# project_vostok__tv_b_gone_extended.net
KiCad netlist of a schematic drawn in EAGLE
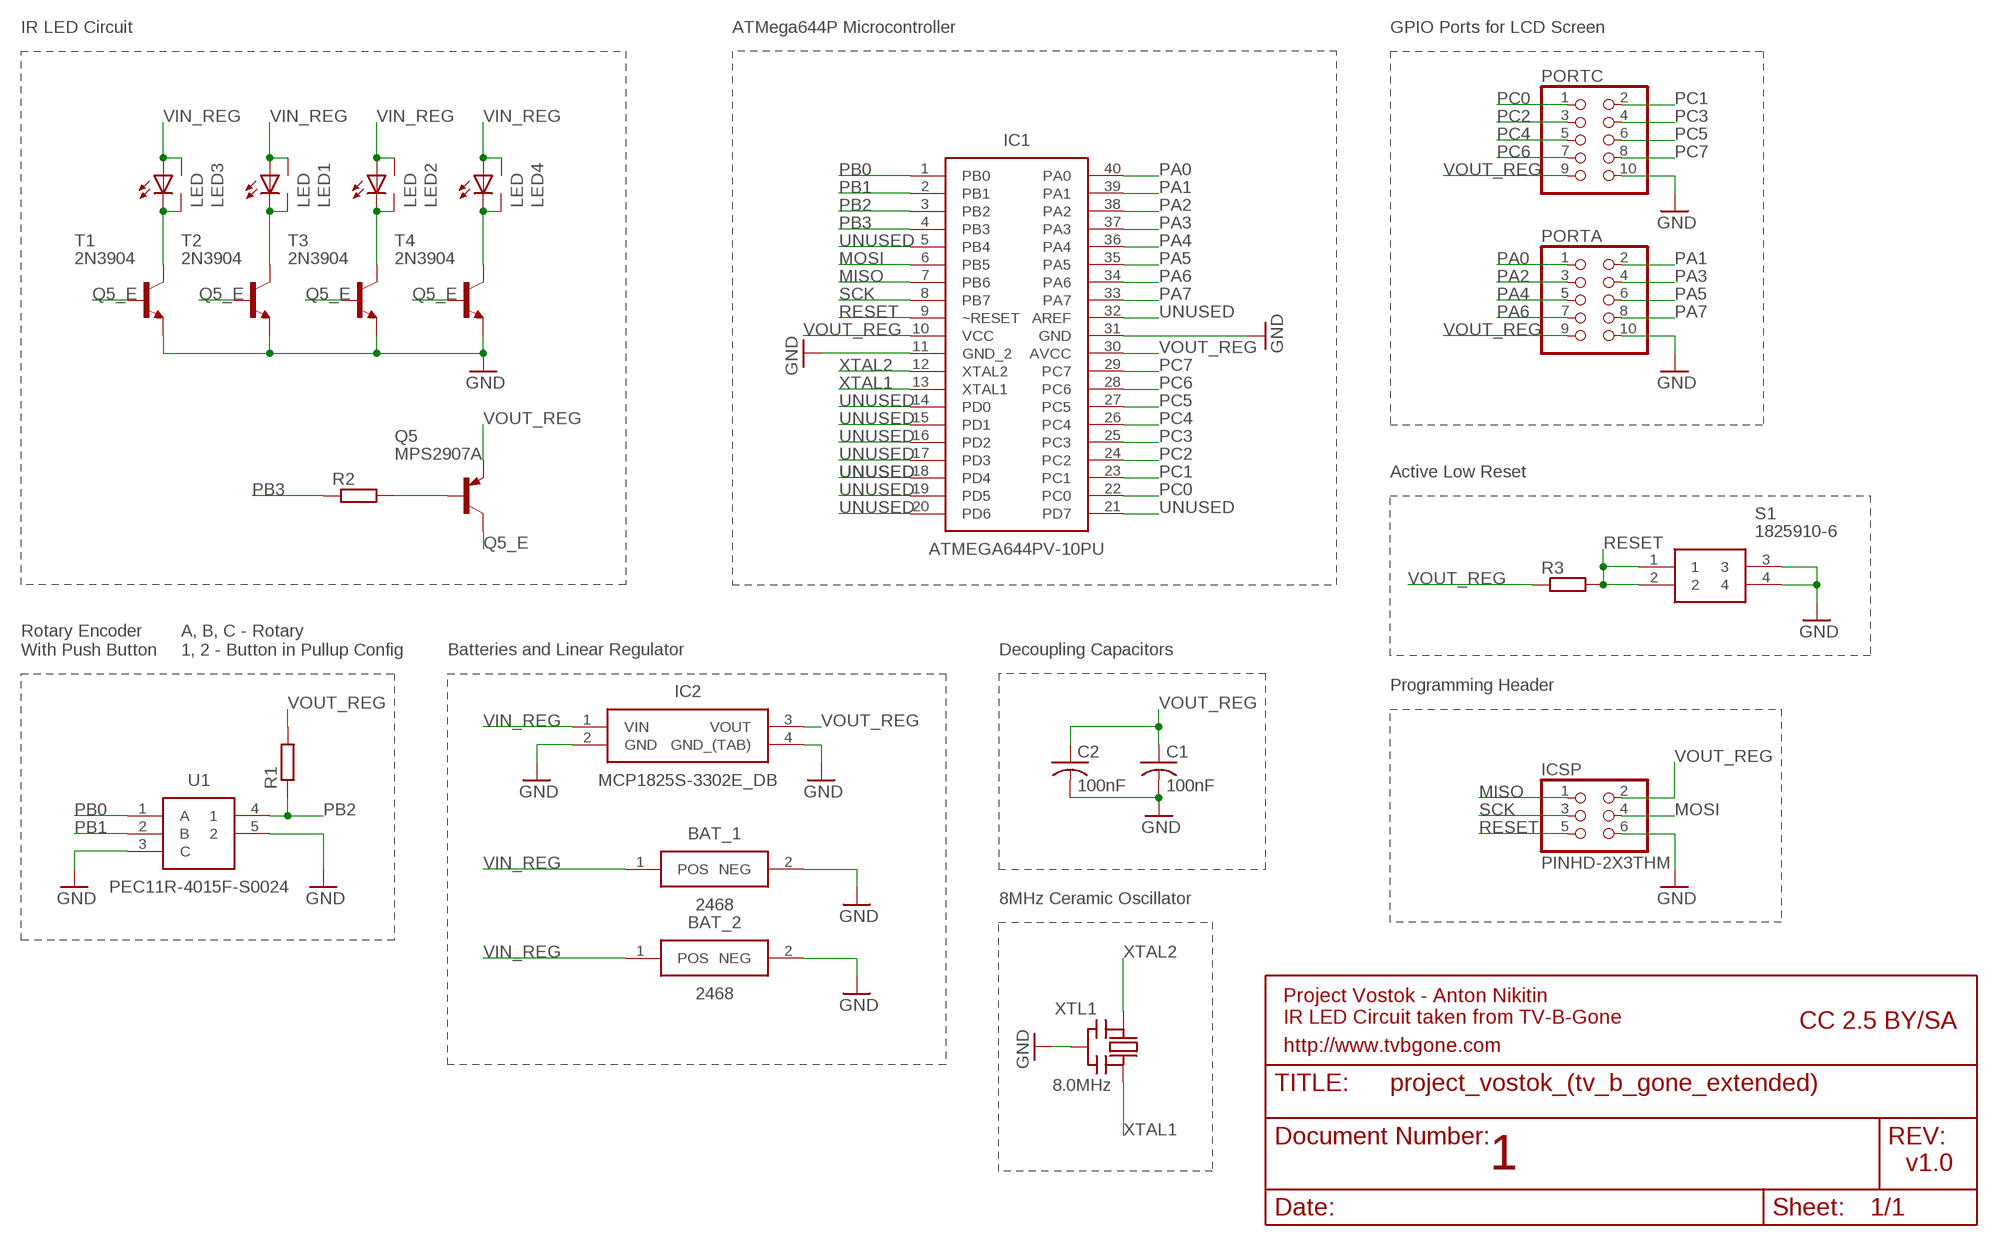
[diagram p0: schematic, sheet 1]

(export (version "E")
  (design (tool "Eeschema 10.0.6"))
  (components
    (comp (ref "BAT_1")
      (value "2468")
      (footprint "eagle-import:2468")
      (fields (field (name "RS_PART_NUMBER") "2794965"))
      (libsource (lib "eagle-import") (part "2468"))
    )
    (comp (ref "BAT_2")
      (value "2468")
      (footprint "eagle-import:2468")
      (fields (field (name "RS_PART_NUMBER") "2794965"))
      (libsource (lib "eagle-import") (part "2468"))
    )
    (comp (ref "C1")
      (value "100nF")
      (footprint "eagle-import:C025-025X050")
      (libsource (lib "eagle-import") (part "C-US025-025X050"))
    )
    (comp (ref "C2")
      (value "100nF")
      (footprint "eagle-import:C025-025X050")
      (libsource (lib "eagle-import") (part "C-US025-025X050"))
    )
    (comp (ref "IC1")
      (value "ATMEGA644PV-10PU")
      (footprint "eagle-import:DIP254P1524X483-40")
      (fields (field (name "RS_PART_NUMBER") "7380491P"))
      (libsource (lib "eagle-import") (part "ATMEGA644PV-10PU"))
    )
    (comp (ref "IC2")
      (value "MCP1825S-3302E_DB")
      (footprint "eagle-import:SOT230P700X180-4N")
      (fields
        (field (name "MANUFACTURER_PART_NUMBER") "MCP1825S-3302E/DB")
        (field (name "RS_PART_NUMBER") "9115520")
      )
      (libsource (lib "eagle-import") (part "MCP1825S-3302E_DB"))
    )
    (comp (ref "ICSP")
      (value "PINHD-2X3THM")
      (footprint "eagle-import:ISP6")
      (libsource (lib "eagle-import") (part "PINHD-2X3THM"))
    )
    (comp (ref "LED1")
      (value "LED")
      (footprint "eagle-import:5MM-SIDE")
      (libsource (lib "eagle-import") (part "LED"))
    )
    (comp (ref "LED2")
      (value "LED")
      (footprint "eagle-import:5MM-SIDE")
      (libsource (lib "eagle-import") (part "LED"))
    )
    (comp (ref "LED3")
      (value "LED")
      (footprint "eagle-import:5MM-SIDE")
      (libsource (lib "eagle-import") (part "LED"))
    )
    (comp (ref "LED4")
      (value "LED")
      (footprint "eagle-import:5MM-SIDE")
      (libsource (lib "eagle-import") (part "LED"))
    )
    (comp (ref "PORTA")
      (value "PINHD-2X5")
      (footprint "eagle-import:2X05")
      (libsource (lib "eagle-import") (part "PINHD-2X5"))
    )
    (comp (ref "PORTC")
      (value "PINHD-2X5")
      (footprint "eagle-import:2X05")
      (libsource (lib "eagle-import") (part "PINHD-2X5"))
    )
    (comp (ref "Q5")
      (value "MPS2907A")
      (footprint "eagle-import:TO92-CBE")
      (libsource (lib "eagle-import") (part "MPS2907A"))
    )
    (comp (ref "R1")
      (value "R-EU_0204/5")
      (footprint "eagle-import:0204_5")
      (libsource (lib "eagle-import") (part "resistor_348_R-EU_0204/5"))
    )
    (comp (ref "R2")
      (value "R-EU_0204/5")
      (footprint "eagle-import:0204_5")
      (libsource (lib "eagle-import") (part "resistor_348_R-EU_0204/5"))
    )
    (comp (ref "R3")
      (value "R-EU_0204/7")
      (footprint "eagle-import:0204_7")
      (libsource (lib "eagle-import") (part "R-EU_0204/7"))
    )
    (comp (ref "S1")
      (value "1825910-6")
      (footprint "eagle-import:1825910-6")
      (fields (field (name "RS_PART_NUMBER") "1613779"))
      (libsource (lib "eagle-import") (part "1825910-6"))
    )
    (comp (ref "T1")
      (value "2N3904")
      (footprint "eagle-import:TO92")
      (libsource (lib "eagle-import") (part "2N3904"))
    )
    (comp (ref "T2")
      (value "2N3904")
      (footprint "eagle-import:TO92")
      (libsource (lib "eagle-import") (part "2N3904"))
    )
    (comp (ref "T3")
      (value "2N3904")
      (footprint "eagle-import:TO92")
      (libsource (lib "eagle-import") (part "2N3904"))
    )
    (comp (ref "T4")
      (value "2N3904")
      (footprint "eagle-import:TO92")
      (libsource (lib "eagle-import") (part "2N3904"))
    )
    (comp (ref "U1")
      (value "PEC11R-4015F-S0024")
      (footprint "eagle-import:PEC12R-4XXXF-SXXXX_1")
      (fields (field (name "RS_PART_NUMBER") "7377739P"))
      (libsource (lib "eagle-import") (part "PEC11R-4015F-S0024"))
    )
    (comp (ref "XTL1")
      (value "8.0MHz")
      (footprint "eagle-import:CERM_OSC")
      (libsource (lib "eagle-import") (part "CERMOSCILL"))
    )
  )
  (nets
    (net (code "1") (name "/MISO") (class "Default")
      (node (ref "IC1") (pin "7") (pinfunction "PB6_7") (pintype "passive"))
      (node (ref "ICSP") (pin "1") (pinfunction "1_1") (pintype "passive"))
    )
    (net (code "2") (name "/MOSI") (class "Default")
      (node (ref "IC1") (pin "6") (pinfunction "PB5_6") (pintype "passive"))
      (node (ref "ICSP") (pin "4") (pinfunction "4_4") (pintype "passive"))
    )
    (net (code "3") (name "/PA0") (class "Default")
      (node (ref "IC1") (pin "40") (pinfunction "PA0_40") (pintype "passive"))
      (node (ref "PORTA") (pin "1") (pinfunction "1_1") (pintype "passive"))
    )
    (net (code "4") (name "/PA1") (class "Default")
      (node (ref "IC1") (pin "39") (pinfunction "PA1_39") (pintype "passive"))
      (node (ref "PORTA") (pin "2") (pinfunction "2_2") (pintype "passive"))
    )
    (net (code "5") (name "/PA2") (class "Default")
      (node (ref "IC1") (pin "38") (pinfunction "PA2_38") (pintype "passive"))
      (node (ref "PORTA") (pin "3") (pinfunction "3_3") (pintype "passive"))
    )
    (net (code "6") (name "/PA3") (class "Default")
      (node (ref "IC1") (pin "37") (pinfunction "PA3_37") (pintype "passive"))
      (node (ref "PORTA") (pin "4") (pinfunction "4_4") (pintype "passive"))
    )
    (net (code "7") (name "/PA4") (class "Default")
      (node (ref "IC1") (pin "36") (pinfunction "PA4_36") (pintype "passive"))
      (node (ref "PORTA") (pin "5") (pinfunction "5_5") (pintype "passive"))
    )
    (net (code "8") (name "/PA5") (class "Default")
      (node (ref "IC1") (pin "35") (pinfunction "PA5_35") (pintype "passive"))
      (node (ref "PORTA") (pin "6") (pinfunction "6_6") (pintype "passive"))
    )
    (net (code "9") (name "/PA6") (class "Default")
      (node (ref "IC1") (pin "34") (pinfunction "PA6_34") (pintype "passive"))
      (node (ref "PORTA") (pin "7") (pinfunction "7_7") (pintype "passive"))
    )
    (net (code "10") (name "/PA7") (class "Default")
      (node (ref "IC1") (pin "33") (pinfunction "PA7_33") (pintype "passive"))
      (node (ref "PORTA") (pin "8") (pinfunction "8_8") (pintype "passive"))
    )
    (net (code "11") (name "/PB0") (class "Default")
      (node (ref "IC1") (pin "1") (pinfunction "PB0_1") (pintype "passive"))
      (node (ref "U1") (pin "1") (pinfunction "A_1") (pintype "passive"))
    )
    (net (code "12") (name "/PB1") (class "Default")
      (node (ref "IC1") (pin "2") (pinfunction "PB1_2") (pintype "passive"))
      (node (ref "U1") (pin "2") (pinfunction "B_2") (pintype "passive"))
    )
    (net (code "13") (name "/PB2") (class "Default")
      (node (ref "IC1") (pin "3") (pinfunction "PB2_3") (pintype "passive"))
      (node (ref "R1") (pin "1") (pinfunction "1_1") (pintype "passive"))
      (node (ref "U1") (pin "4") (pinfunction "1_4") (pintype "passive"))
    )
    (net (code "14") (name "/PB3") (class "Default")
      (node (ref "IC1") (pin "4") (pinfunction "PB3_4") (pintype "passive"))
      (node (ref "R2") (pin "1") (pinfunction "1_1") (pintype "passive"))
    )
    (net (code "15") (name "/PC0") (class "Default")
      (node (ref "IC1") (pin "22") (pinfunction "PC0_22") (pintype "passive"))
      (node (ref "PORTC") (pin "1") (pinfunction "1_1") (pintype "passive"))
    )
    (net (code "16") (name "/PC1") (class "Default")
      (node (ref "IC1") (pin "23") (pinfunction "PC1_23") (pintype "passive"))
      (node (ref "PORTC") (pin "2") (pinfunction "2_2") (pintype "passive"))
    )
    (net (code "17") (name "/PC2") (class "Default")
      (node (ref "IC1") (pin "24") (pinfunction "PC2_24") (pintype "passive"))
      (node (ref "PORTC") (pin "3") (pinfunction "3_3") (pintype "passive"))
    )
    (net (code "18") (name "/PC3") (class "Default")
      (node (ref "IC1") (pin "25") (pinfunction "PC3_25") (pintype "passive"))
      (node (ref "PORTC") (pin "4") (pinfunction "4_4") (pintype "passive"))
    )
    (net (code "19") (name "/PC4") (class "Default")
      (node (ref "IC1") (pin "26") (pinfunction "PC4_26") (pintype "passive"))
      (node (ref "PORTC") (pin "5") (pinfunction "5_5") (pintype "passive"))
    )
    (net (code "20") (name "/PC5") (class "Default")
      (node (ref "IC1") (pin "27") (pinfunction "PC5_27") (pintype "passive"))
      (node (ref "PORTC") (pin "6") (pinfunction "6_6") (pintype "passive"))
    )
    (net (code "21") (name "/PC6") (class "Default")
      (node (ref "IC1") (pin "28") (pinfunction "PC6_28") (pintype "passive"))
      (node (ref "PORTC") (pin "7") (pinfunction "7_7") (pintype "passive"))
    )
    (net (code "22") (name "/PC7") (class "Default")
      (node (ref "IC1") (pin "29") (pinfunction "PC7_29") (pintype "passive"))
      (node (ref "PORTC") (pin "8") (pinfunction "8_8") (pintype "passive"))
    )
    (net (code "23") (name "/Q5_E") (class "Default")
      (node (ref "Q5") (pin "C") (pinfunction "C_C") (pintype "passive"))
      (node (ref "T1") (pin "2") (pinfunction "B_2") (pintype "passive"))
      (node (ref "T2") (pin "2") (pinfunction "B_2") (pintype "passive"))
      (node (ref "T3") (pin "2") (pinfunction "B_2") (pintype "passive"))
      (node (ref "T4") (pin "2") (pinfunction "B_2") (pintype "passive"))
    )
    (net (code "24") (name "/RESET") (class "Default")
      (node (ref "IC1") (pin "9") (pinfunction "~{RESET}_9") (pintype "passive"))
      (node (ref "ICSP") (pin "5") (pinfunction "5_5") (pintype "passive"))
      (node (ref "R3") (pin "2") (pinfunction "2_2") (pintype "passive"))
      (node (ref "S1") (pin "1") (pinfunction "1_1") (pintype "input"))
      (node (ref "S1") (pin "2") (pinfunction "2_2") (pintype "input"))
    )
    (net (code "25") (name "/SCK") (class "Default")
      (node (ref "IC1") (pin "8") (pinfunction "PB7_8") (pintype "passive"))
      (node (ref "ICSP") (pin "3") (pinfunction "3_3") (pintype "passive"))
    )
    (net (code "26") (name "/VIN_REG") (class "Default")
      (node (ref "BAT_1") (pin "1") (pinfunction "POS_1") (pintype "passive"))
      (node (ref "BAT_2") (pin "1") (pinfunction "POS_1") (pintype "passive"))
      (node (ref "IC2") (pin "1") (pinfunction "VIN_1") (pintype "input"))
      (node (ref "LED1") (pin "A") (pinfunction "A_A") (pintype "passive"))
      (node (ref "LED1") (pin "A2") (pinfunction "A1_A2") (pintype "passive"))
      (node (ref "LED2") (pin "A") (pinfunction "A_A") (pintype "passive"))
      (node (ref "LED2") (pin "A2") (pinfunction "A1_A2") (pintype "passive"))
      (node (ref "LED3") (pin "A") (pinfunction "A_A") (pintype "passive"))
      (node (ref "LED3") (pin "A2") (pinfunction "A1_A2") (pintype "passive"))
      (node (ref "LED4") (pin "A") (pinfunction "A_A") (pintype "passive"))
      (node (ref "LED4") (pin "A2") (pinfunction "A1_A2") (pintype "passive"))
    )
    (net (code "27") (name "/VOUT_REG") (class "Default")
      (node (ref "C1") (pin "1") (pinfunction "1_1") (pintype "passive"))
      (node (ref "C2") (pin "1") (pinfunction "1_1") (pintype "passive"))
      (node (ref "IC1") (pin "10") (pinfunction "VCC_10") (pintype "passive"))
      (node (ref "IC1") (pin "30") (pinfunction "AVCC_30") (pintype "passive"))
      (node (ref "IC2") (pin "3") (pinfunction "VOUT_3") (pintype "output"))
      (node (ref "ICSP") (pin "2") (pinfunction "2_2") (pintype "passive"))
      (node (ref "PORTA") (pin "9") (pinfunction "9_9") (pintype "passive"))
      (node (ref "PORTC") (pin "9") (pinfunction "9_9") (pintype "passive"))
      (node (ref "Q5") (pin "E") (pinfunction "E_E") (pintype "passive"))
      (node (ref "R1") (pin "2") (pinfunction "2_2") (pintype "passive"))
      (node (ref "R3") (pin "1") (pinfunction "1_1") (pintype "passive"))
    )
    (net (code "28") (name "/XTAL1") (class "Default")
      (node (ref "IC1") (pin "13") (pinfunction "XTAL1_13") (pintype "passive"))
      (node (ref "XTL1") (pin "P$3") (pinfunction "OUT_P$3") (pintype "bidirectional"))
    )
    (net (code "29") (name "/XTAL2") (class "Default")
      (node (ref "IC1") (pin "12") (pinfunction "XTAL2_12") (pintype "passive"))
      (node (ref "XTL1") (pin "P$1") (pinfunction "IN_P$1") (pintype "bidirectional"))
    )
    (net (code "30") (name "GND") (class "Default")
      (node (ref "BAT_1") (pin "2") (pinfunction "NEG_2") (pintype "passive"))
      (node (ref "BAT_2") (pin "2") (pinfunction "NEG_2") (pintype "passive"))
      (node (ref "C1") (pin "2") (pinfunction "2_2") (pintype "passive"))
      (node (ref "C2") (pin "2") (pinfunction "2_2") (pintype "passive"))
      (node (ref "IC1") (pin "11") (pinfunction "GND_2_11") (pintype "passive"))
      (node (ref "IC1") (pin "31") (pinfunction "GND_31") (pintype "passive"))
      (node (ref "IC2") (pin "2") (pinfunction "GND_2") (pintype "power_in"))
      (node (ref "IC2") (pin "4") (pinfunction "GND_(TAB)_4") (pintype "power_in"))
      (node (ref "ICSP") (pin "6") (pinfunction "6_6") (pintype "passive"))
      (node (ref "PORTA") (pin "10") (pinfunction "10_10") (pintype "passive"))
      (node (ref "PORTC") (pin "10") (pinfunction "10_10") (pintype "passive"))
      (node (ref "S1") (pin "3") (pinfunction "3_3") (pintype "input"))
      (node (ref "S1") (pin "4") (pinfunction "4_4") (pintype "input"))
      (node (ref "T1") (pin "3") (pinfunction "E_3") (pintype "passive"))
      (node (ref "T2") (pin "3") (pinfunction "E_3") (pintype "passive"))
      (node (ref "T3") (pin "3") (pinfunction "E_3") (pintype "passive"))
      (node (ref "T4") (pin "3") (pinfunction "E_3") (pintype "passive"))
      (node (ref "U1") (pin "3") (pinfunction "C_3") (pintype "passive"))
      (node (ref "U1") (pin "5") (pinfunction "2_5") (pintype "passive"))
      (node (ref "XTL1") (pin "P$2") (pinfunction "GND_P$2") (pintype "bidirectional"))
    )
    (net (code "31") (name "Net-(LED1-C)") (class "Default")
      (node (ref "LED1") (pin "K") (pinfunction "C_K") (pintype "passive"))
      (node (ref "LED1") (pin "K2") (pinfunction "C1_K2") (pintype "passive"))
      (node (ref "T2") (pin "1") (pinfunction "C_1") (pintype "passive"))
    )
    (net (code "32") (name "Net-(LED2-C)") (class "Default")
      (node (ref "LED2") (pin "K") (pinfunction "C_K") (pintype "passive"))
      (node (ref "LED2") (pin "K2") (pinfunction "C1_K2") (pintype "passive"))
      (node (ref "T3") (pin "1") (pinfunction "C_1") (pintype "passive"))
    )
    (net (code "33") (name "Net-(LED3-C)") (class "Default")
      (node (ref "LED3") (pin "K") (pinfunction "C_K") (pintype "passive"))
      (node (ref "LED3") (pin "K2") (pinfunction "C1_K2") (pintype "passive"))
      (node (ref "T1") (pin "1") (pinfunction "C_1") (pintype "passive"))
    )
    (net (code "34") (name "Net-(LED4-C)") (class "Default")
      (node (ref "LED4") (pin "K") (pinfunction "C_K") (pintype "passive"))
      (node (ref "LED4") (pin "K2") (pinfunction "C1_K2") (pintype "passive"))
      (node (ref "T4") (pin "1") (pinfunction "C_1") (pintype "passive"))
    )
    (net (code "35") (name "Net-(Q5-PadB)") (class "Default")
      (node (ref "Q5") (pin "B") (pinfunction "B_B") (pintype "passive"))
      (node (ref "R2") (pin "2") (pinfunction "2_2") (pintype "passive"))
    )
    (net (code "36") (name "unconnected-(IC1-AREF-Pad32)") (class "Default")
      (node (ref "IC1") (pin "32") (pinfunction "AREF_32") (pintype "passive"))
    )
    (net (code "37") (name "unconnected-(IC1-PB4-Pad5)") (class "Default")
      (node (ref "IC1") (pin "5") (pinfunction "PB4_5") (pintype "passive"))
    )
    (net (code "38") (name "unconnected-(IC1-PD0-Pad14)") (class "Default")
      (node (ref "IC1") (pin "14") (pinfunction "PD0_14") (pintype "passive"))
    )
    (net (code "39") (name "unconnected-(IC1-PD1-Pad15)") (class "Default")
      (node (ref "IC1") (pin "15") (pinfunction "PD1_15") (pintype "passive"))
    )
    (net (code "40") (name "unconnected-(IC1-PD2-Pad16)") (class "Default")
      (node (ref "IC1") (pin "16") (pinfunction "PD2_16") (pintype "passive"))
    )
    (net (code "41") (name "unconnected-(IC1-PD3-Pad17)") (class "Default")
      (node (ref "IC1") (pin "17") (pinfunction "PD3_17") (pintype "passive"))
    )
    (net (code "42") (name "unconnected-(IC1-PD4-Pad18)") (class "Default")
      (node (ref "IC1") (pin "18") (pinfunction "PD4_18") (pintype "passive"))
    )
    (net (code "43") (name "unconnected-(IC1-PD5-Pad19)") (class "Default")
      (node (ref "IC1") (pin "19") (pinfunction "PD5_19") (pintype "passive"))
    )
    (net (code "44") (name "unconnected-(IC1-PD6-Pad20)") (class "Default")
      (node (ref "IC1") (pin "20") (pinfunction "PD6_20") (pintype "passive"))
    )
    (net (code "45") (name "unconnected-(IC1-PD7-Pad21)") (class "Default")
      (node (ref "IC1") (pin "21") (pinfunction "PD7_21") (pintype "passive"))
    )
  )
)
